# AFE_Chip.net
KiCad netlist of a schematic drawn in Altium Designer
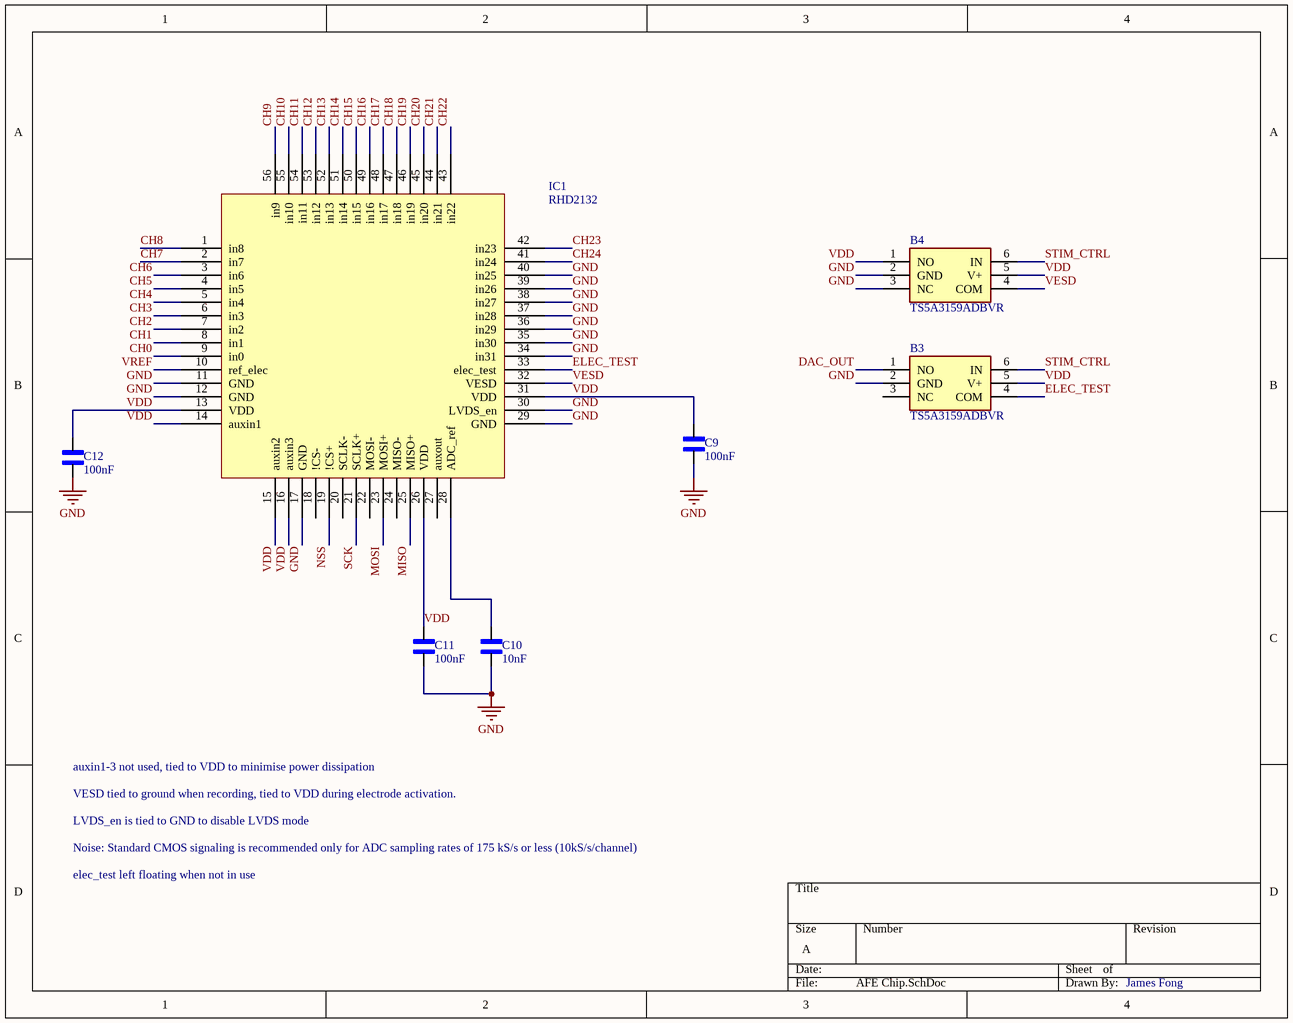
[diagram p0: AFE Chip.SchDoc]

(export (version "E")
  (design (tool "Eeschema 10.0.6"))
  (components
    (comp (ref "B3")
      (value "TS5A3159ADBVR")
      (footprint "SOT95P280X145-6N")
      (description "1 Ohm SPDT Analog Switch 5-V/3.3-V Single Channel 2:1 Multiplexer/Demultiplexer")
      (libsource (lib "James' Workspace") (part "TS5A3159ADBVR"))
    )
    (comp (ref "B4")
      (value "TS5A3159ADBVR")
      (footprint "SOT95P280X145-6N")
      (description "1 Ohm SPDT Analog Switch 5-V/3.3-V Single Channel 2:1 Multiplexer/Demultiplexer")
      (libsource (lib "James' Workspace") (part "TS5A3159ADBVR"))
    )
    (comp (ref "C9")
      (value "100nF")
      (footprint "CAPC2012X88N")
      (description "0.1 ÂµF Â±10% 35V Ceramic Capacitor X7R 0805 (2012 Metric)")
      (fields (field (name "MP") "C0805C104K6RACTU") (field (name "MF") "KEMET"))
      (libsource (lib "James' Workspace") (part "C0805C104K6RACTU"))
    )
    (comp (ref "C10")
      (value "10nF")
      (footprint "CAPC2012X88N")
      (description "Capacitor;Ceramic;Cap 0.01uF;Tol 5%;Vol-Rtg 50 V;SMT;Case 0805;X7R;TR")
      (fields (field (name "MP") "C0805C103J5RACTU") (field (name "MF") "KEMET"))
      (libsource (lib "James' Workspace") (part "C0805C103J5RACTU"))
    )
    (comp (ref "C11")
      (value "100nF")
      (footprint "CAPC2012X88N")
      (description "0.1 ÂµF Â±10% 35V Ceramic Capacitor X7R 0805 (2012 Metric)")
      (fields (field (name "MP") "C0805C104K6RACTU") (field (name "MF") "KEMET"))
      (libsource (lib "James' Workspace") (part "C0805C104K6RACTU"))
    )
    (comp (ref "C12")
      (value "100nF")
      (footprint "CAPC2012X88N")
      (description "0.1 ÂµF Â±10% 35V Ceramic Capacitor X7R 0805 (2012 Metric)")
      (fields (field (name "MP") "C0805C104K6RACTU") (field (name "MF") "KEMET"))
      (libsource (lib "James' Workspace") (part "C0805C104K6RACTU"))
    )
    (comp (ref "IC1") (value "RHD2132") (footprint "RHD2216") (libsource (lib "RHD2132") (part "RHD2132")))
  )
  (nets
    (net (code "1") (name "/CH0") (class "Default")
      (node (ref "IC1") (pin "9") (pinfunction "in0_9") (pintype "passive"))
    )
    (net (code "2") (name "/CH1") (class "Default")
      (node (ref "IC1") (pin "8") (pinfunction "in1_8") (pintype "passive"))
    )
    (net (code "3") (name "/CH2") (class "Default")
      (node (ref "IC1") (pin "7") (pinfunction "in2_7") (pintype "passive"))
    )
    (net (code "4") (name "/CH3") (class "Default")
      (node (ref "IC1") (pin "6") (pinfunction "in3_6") (pintype "passive"))
    )
    (net (code "5") (name "/CH4") (class "Default")
      (node (ref "IC1") (pin "5") (pinfunction "in4_5") (pintype "passive"))
    )
    (net (code "6") (name "/CH5") (class "Default")
      (node (ref "IC1") (pin "4") (pinfunction "in5_4") (pintype "passive"))
    )
    (net (code "7") (name "/CH6") (class "Default")
      (node (ref "IC1") (pin "3") (pinfunction "in6_3") (pintype "passive"))
    )
    (net (code "8") (name "/CH7") (class "Default")
      (node (ref "IC1") (pin "2") (pinfunction "in7_2") (pintype "passive"))
    )
    (net (code "9") (name "/CH8") (class "Default")
      (node (ref "IC1") (pin "1") (pinfunction "in8_1") (pintype "passive"))
    )
    (net (code "10") (name "/CH9") (class "Default")
      (node (ref "IC1") (pin "56") (pinfunction "in9_56") (pintype "passive"))
    )
    (net (code "11") (name "/CH10") (class "Default")
      (node (ref "IC1") (pin "55") (pinfunction "in10_55") (pintype "passive"))
    )
    (net (code "12") (name "/CH11") (class "Default")
      (node (ref "IC1") (pin "54") (pinfunction "in11_54") (pintype "passive"))
    )
    (net (code "13") (name "/CH12") (class "Default")
      (node (ref "IC1") (pin "53") (pinfunction "in12_53") (pintype "passive"))
    )
    (net (code "14") (name "/CH13") (class "Default")
      (node (ref "IC1") (pin "52") (pinfunction "in13_52") (pintype "passive"))
    )
    (net (code "15") (name "/CH14") (class "Default")
      (node (ref "IC1") (pin "51") (pinfunction "in14_51") (pintype "passive"))
    )
    (net (code "16") (name "/CH15") (class "Default")
      (node (ref "IC1") (pin "50") (pinfunction "in15_50") (pintype "passive"))
    )
    (net (code "17") (name "/CH16") (class "Default")
      (node (ref "IC1") (pin "49") (pinfunction "in16_49") (pintype "passive"))
    )
    (net (code "18") (name "/CH17") (class "Default")
      (node (ref "IC1") (pin "48") (pinfunction "in17_48") (pintype "passive"))
    )
    (net (code "19") (name "/CH18") (class "Default")
      (node (ref "IC1") (pin "47") (pinfunction "in18_47") (pintype "passive"))
    )
    (net (code "20") (name "/CH19") (class "Default")
      (node (ref "IC1") (pin "46") (pinfunction "in19_46") (pintype "passive"))
    )
    (net (code "21") (name "/CH20") (class "Default")
      (node (ref "IC1") (pin "45") (pinfunction "in20_45") (pintype "passive"))
    )
    (net (code "22") (name "/CH21") (class "Default")
      (node (ref "IC1") (pin "44") (pinfunction "in21_44") (pintype "passive"))
    )
    (net (code "23") (name "/CH22") (class "Default")
      (node (ref "IC1") (pin "43") (pinfunction "in22_43") (pintype "passive"))
    )
    (net (code "24") (name "/CH23") (class "Default")
      (node (ref "IC1") (pin "42") (pinfunction "in23_42") (pintype "passive"))
    )
    (net (code "25") (name "/CH24") (class "Default")
      (node (ref "IC1") (pin "41") (pinfunction "in24_41") (pintype "passive"))
    )
    (net (code "26") (name "/DAC_OUT") (class "Default")
      (node (ref "B3") (pin "1") (pinfunction "NO_1") (pintype "passive"))
    )
    (net (code "27") (name "/ELEC_TEST") (class "Default")
      (node (ref "B3") (pin "4") (pinfunction "COM_4") (pintype "passive"))
      (node (ref "IC1") (pin "33") (pinfunction "elec_test_33") (pintype "passive"))
    )
    (net (code "28") (name "/MISO") (class "Default")
      (node (ref "IC1") (pin "25") (pinfunction "MISO+_25") (pintype "passive"))
    )
    (net (code "29") (name "/MOSI") (class "Default")
      (node (ref "IC1") (pin "23") (pinfunction "MOSI+_23") (pintype "passive"))
    )
    (net (code "30") (name "/NSS") (class "Default")
      (node (ref "IC1") (pin "19") (pinfunction "!CS+_19") (pintype "passive"))
    )
    (net (code "31") (name "/SCK") (class "Default")
      (node (ref "IC1") (pin "21") (pinfunction "SCLK+_21") (pintype "passive"))
    )
    (net (code "32") (name "/STIM_CTRL") (class "Default")
      (node (ref "B3") (pin "6") (pinfunction "IN_6") (pintype "passive"))
      (node (ref "B4") (pin "6") (pinfunction "IN_6") (pintype "passive"))
    )
    (net (code "33") (name "/VDD") (class "Default")
      (node (ref "B3") (pin "5") (pinfunction "V+_5") (pintype "passive"))
      (node (ref "B4") (pin "1") (pinfunction "NO_1") (pintype "passive"))
      (node (ref "B4") (pin "5") (pinfunction "V+_5") (pintype "passive"))
      (node (ref "C11") (pin "2") (pinfunction "2_2") (pintype "passive"))
      (node (ref "C12") (pin "2") (pinfunction "2_2") (pintype "passive"))
      (node (ref "C9") (pin "2") (pinfunction "2_2") (pintype "passive"))
      (node (ref "IC1") (pin "13") (pinfunction "VDD_13") (pintype "passive"))
      (node (ref "IC1") (pin "14") (pinfunction "auxin1_14") (pintype "passive"))
      (node (ref "IC1") (pin "15") (pinfunction "auxin2_15") (pintype "passive"))
      (node (ref "IC1") (pin "16") (pinfunction "auxin3_16") (pintype "passive"))
      (node (ref "IC1") (pin "26") (pinfunction "VDD_26") (pintype "passive"))
      (node (ref "IC1") (pin "31") (pinfunction "VDD_31") (pintype "passive"))
    )
    (net (code "34") (name "/VESD") (class "Default")
      (node (ref "B4") (pin "4") (pinfunction "COM_4") (pintype "passive"))
      (node (ref "IC1") (pin "32") (pinfunction "VESD_32") (pintype "passive"))
    )
    (net (code "35") (name "/VREF") (class "Default")
      (node (ref "IC1") (pin "10") (pinfunction "ref_elec_10") (pintype "passive"))
    )
    (net (code "36") (name "GND") (class "Default")
      (node (ref "B3") (pin "2") (pinfunction "GND_2") (pintype "passive"))
      (node (ref "B4") (pin "2") (pinfunction "GND_2") (pintype "passive"))
      (node (ref "B4") (pin "3") (pinfunction "NC_3") (pintype "passive"))
      (node (ref "C10") (pin "1") (pinfunction "1_1") (pintype "passive"))
      (node (ref "C11") (pin "1") (pinfunction "1_1") (pintype "passive"))
      (node (ref "C12") (pin "1") (pinfunction "1_1") (pintype "passive"))
      (node (ref "C9") (pin "1") (pinfunction "1_1") (pintype "passive"))
      (node (ref "IC1") (pin "11") (pinfunction "GND_11") (pintype "passive"))
      (node (ref "IC1") (pin "12") (pinfunction "GND_12") (pintype "passive"))
      (node (ref "IC1") (pin "17") (pinfunction "GND_17") (pintype "passive"))
      (node (ref "IC1") (pin "29") (pinfunction "GND_29") (pintype "passive"))
      (node (ref "IC1") (pin "30") (pinfunction "LVDS_en_30") (pintype "passive"))
      (node (ref "IC1") (pin "34") (pinfunction "in31_34") (pintype "passive"))
      (node (ref "IC1") (pin "35") (pinfunction "in30_35") (pintype "passive"))
      (node (ref "IC1") (pin "36") (pinfunction "in29_36") (pintype "passive"))
      (node (ref "IC1") (pin "37") (pinfunction "in28_37") (pintype "passive"))
      (node (ref "IC1") (pin "38") (pinfunction "in27_38") (pintype "passive"))
      (node (ref "IC1") (pin "39") (pinfunction "in26_39") (pintype "passive"))
      (node (ref "IC1") (pin "40") (pinfunction "in25_40") (pintype "passive"))
    )
    (net (code "37") (name "Net-(IC1-ADC_ref)") (class "Default")
      (node (ref "C10") (pin "2") (pinfunction "2_2") (pintype "passive"))
      (node (ref "IC1") (pin "28") (pinfunction "ADC_ref_28") (pintype "passive"))
    )
    (net (code "38") (name "unconnected-(B3-NC-Pad3)") (class "Default")
      (node (ref "B3") (pin "3") (pinfunction "NC_3") (pintype "passive"))
    )
    (net (code "39") (name "unconnected-(IC1-!CS--Pad18)") (class "Default")
      (node (ref "IC1") (pin "18") (pinfunction "!CS-_18") (pintype "passive"))
    )
    (net (code "40") (name "unconnected-(IC1-MISO--Pad24)") (class "Default")
      (node (ref "IC1") (pin "24") (pinfunction "MISO-_24") (pintype "passive"))
    )
    (net (code "41") (name "unconnected-(IC1-MOSI--Pad22)") (class "Default")
      (node (ref "IC1") (pin "22") (pinfunction "MOSI-_22") (pintype "passive"))
    )
    (net (code "42") (name "unconnected-(IC1-SCLK--Pad20)") (class "Default")
      (node (ref "IC1") (pin "20") (pinfunction "SCLK-_20") (pintype "passive"))
    )
    (net (code "43") (name "unconnected-(IC1-auxout-Pad27)") (class "Default")
      (node (ref "IC1") (pin "27") (pinfunction "auxout_27") (pintype "passive"))
    )
  )
)
